# design.net
KiCad netlist of a schematic drawn in Altium Designer
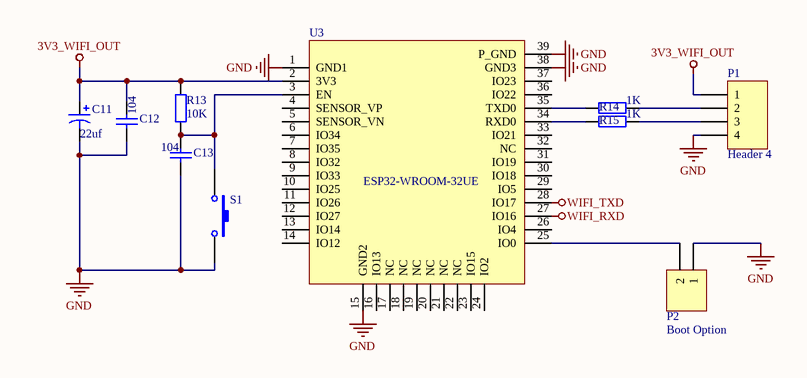
[diagram p0: 转接板.SchDoc]

(export (version "E")
  (design (tool "Eeschema 10.0.6"))
  (components
    (comp (ref "C11")
      (value "22uf")
      (footprint "RB7.6-15")
      (description "Polarized Capacitor (Radial)")
      (fields (field (name "Comment") "Cap Pol1") (field (name "PUBLISHER") "Altium Limited"))
      (libsource (lib "Miscellaneous Devices") (part "Cap Pol1"))
    )
    (comp (ref "C12")
      (value "104")
      (footprint "0805-JT")
      (description "Capacitor")
      (fields (field (name "Comment") "Cap") (field (name "PUBLISHER") "Altium Limited"))
      (libsource (lib "Miscellaneous Devices") (part "Cap"))
    )
    (comp (ref "C13")
      (value "104")
      (footprint "0805-JT")
      (description "Capacitor")
      (fields (field (name "Comment") "Cap") (field (name "PUBLISHER") "Altium Limited"))
      (libsource (lib "Miscellaneous Devices") (part "Cap"))
    )
    (comp (ref "P1")
      (value "Header 4")
      (footprint "HDR1X4")
      (description "Header, 4-Pin")
      (fields (field (name "PUBLISHER") "Altium Limited"))
      (libsource (lib "Miscellaneous Connectors") (part "Header 4"))
    )
    (comp (ref "P2")
      (value "Boot Option")
      (footprint "HDR1X2")
      (description "Header, 2-Pin")
      (fields (field (name "PUBLISHER") "Altium Limited"))
      (libsource (lib "Miscellaneous Connectors") (part "Header 2"))
    )
    (comp (ref "R13")
      (value "10K")
      (footprint "0603-JT")
      (description "Resistor")
      (fields (field (name "Comment") "Res2") (field (name "PUBLISHER") "Altium Limited"))
      (libsource (lib "") (part "Res2_1"))
    )
    (comp (ref "R14")
      (value "1K")
      (footprint "0603-JT")
      (description "Resistor")
      (fields (field (name "Comment") "Res2") (field (name "PUBLISHER") "Altium Limited"))
      (libsource (lib "Miscellaneous Devices") (part "Res2"))
    )
    (comp (ref "R15")
      (value "1K")
      (footprint "0603-JT")
      (description "Resistor")
      (fields (field (name "Comment") "Res2") (field (name "PUBLISHER") "Altium Limited"))
      (libsource (lib "Miscellaneous Devices") (part "Res2"))
    )
    (comp (ref "S1")
      (value "SW-PB")
      (footprint "SPST-2")
      (description "Switch")
      (fields (field (name "PUBLISHER") "Altium Limited"))
      (libsource (lib "Miscellaneous Devices") (part "SW-PB"))
    )
    (comp (ref "U3")
      (value "ESP32-WROOM-32UE")
      (description "ESP32 wifi模块 IPEX接口天线")
      (libsource (lib "原理图库") (part "ESP32-WROOM-32UE"))
    )
  )
  (nets
    (net (code "1") (name "3V3_WIFI_OUT") (class "Default")
      (node (ref "C11") (pin "1") (pinfunction "1_1") (pintype "passive"))
      (node (ref "C12") (pin "2") (pinfunction "2_2") (pintype "passive"))
      (node (ref "P1") (pin "1") (pinfunction "1_1") (pintype "passive"))
      (node (ref "R13") (pin "1") (pinfunction "1_1") (pintype "passive"))
      (node (ref "U3") (pin "2") (pinfunction "3V3_2") (pintype "passive"))
    )
    (net (code "2") (name "GND") (class "Default")
      (node (ref "C11") (pin "2") (pinfunction "2_2") (pintype "passive"))
      (node (ref "C12") (pin "1") (pinfunction "1_1") (pintype "passive"))
      (node (ref "C13") (pin "1") (pinfunction "1_1") (pintype "passive"))
      (node (ref "P1") (pin "4") (pinfunction "4_4") (pintype "passive"))
      (node (ref "P2") (pin "1") (pinfunction "1_1") (pintype "passive"))
      (node (ref "S1") (pin "2") (pinfunction "2_2") (pintype "passive"))
      (node (ref "U3") (pin "1") (pinfunction "GND1_1") (pintype "passive"))
      (node (ref "U3") (pin "15") (pinfunction "GND2_15") (pintype "passive"))
      (node (ref "U3") (pin "38") (pinfunction "GND3_38") (pintype "passive"))
      (node (ref "U3") (pin "39") (pinfunction "P_GND_39") (pintype "passive"))
    )
    (net (code "3") (name "Net-(P1-Pad2)") (class "Default")
      (node (ref "P1") (pin "2") (pinfunction "2_2") (pintype "passive"))
      (node (ref "R14") (pin "2") (pinfunction "2_2") (pintype "passive"))
    )
    (net (code "4") (name "Net-(P1-Pad3)") (class "Default")
      (node (ref "P1") (pin "3") (pinfunction "3_3") (pintype "passive"))
      (node (ref "R15") (pin "2") (pinfunction "2_2") (pintype "passive"))
    )
    (net (code "5") (name "Net-(U3-EN)") (class "Default")
      (node (ref "C13") (pin "2") (pinfunction "2_2") (pintype "passive"))
      (node (ref "R13") (pin "2") (pinfunction "2_2") (pintype "passive"))
      (node (ref "S1") (pin "1") (pinfunction "1_1") (pintype "passive"))
      (node (ref "U3") (pin "3") (pinfunction "EN_3") (pintype "passive"))
    )
    (net (code "6") (name "Net-(U3-IO0)") (class "Default")
      (node (ref "P2") (pin "2") (pinfunction "2_2") (pintype "passive"))
      (node (ref "U3") (pin "25") (pinfunction "IO0_25") (pintype "passive"))
    )
    (net (code "7") (name "Net-(U3-RXD0)") (class "Default")
      (node (ref "R15") (pin "1") (pinfunction "1_1") (pintype "passive"))
      (node (ref "U3") (pin "34") (pinfunction "RXD0_34") (pintype "passive"))
    )
    (net (code "8") (name "Net-(U3-TXD0)") (class "Default")
      (node (ref "R14") (pin "1") (pinfunction "1_1") (pintype "passive"))
      (node (ref "U3") (pin "35") (pinfunction "TXD0_35") (pintype "passive"))
    )
    (net (code "9") (name "WIFI_RXD") (class "Default")
      (node (ref "U3") (pin "27") (pinfunction "IO16_27") (pintype "passive"))
    )
    (net (code "10") (name "WIFI_TXD") (class "Default")
      (node (ref "U3") (pin "28") (pinfunction "IO17_28") (pintype "passive"))
    )
    (net (code "11") (name "unconnected-(U3-IO2-Pad24)") (class "Default")
      (node (ref "U3") (pin "24") (pinfunction "IO2_24") (pintype "passive"))
    )
    (net (code "12") (name "unconnected-(U3-IO4-Pad26)") (class "Default")
      (node (ref "U3") (pin "26") (pinfunction "IO4_26") (pintype "passive"))
    )
    (net (code "13") (name "unconnected-(U3-IO5-Pad29)") (class "Default")
      (node (ref "U3") (pin "29") (pinfunction "IO5_29") (pintype "passive"))
    )
    (net (code "14") (name "unconnected-(U3-IO12-Pad14)") (class "Default")
      (node (ref "U3") (pin "14") (pinfunction "IO12_14") (pintype "passive"))
    )
    (net (code "15") (name "unconnected-(U3-IO13-Pad16)") (class "Default")
      (node (ref "U3") (pin "16") (pinfunction "IO13_16") (pintype "passive"))
    )
    (net (code "16") (name "unconnected-(U3-IO14-Pad13)") (class "Default")
      (node (ref "U3") (pin "13") (pinfunction "IO14_13") (pintype "passive"))
    )
    (net (code "17") (name "unconnected-(U3-IO15-Pad23)") (class "Default")
      (node (ref "U3") (pin "23") (pinfunction "IO15_23") (pintype "passive"))
    )
    (net (code "18") (name "unconnected-(U3-IO18-Pad30)") (class "Default")
      (node (ref "U3") (pin "30") (pinfunction "IO18_30") (pintype "passive"))
    )
    (net (code "19") (name "unconnected-(U3-IO19-Pad31)") (class "Default")
      (node (ref "U3") (pin "31") (pinfunction "IO19_31") (pintype "passive"))
    )
    (net (code "20") (name "unconnected-(U3-IO21-Pad33)") (class "Default")
      (node (ref "U3") (pin "33") (pinfunction "IO21_33") (pintype "passive"))
    )
    (net (code "21") (name "unconnected-(U3-IO22-Pad36)") (class "Default")
      (node (ref "U3") (pin "36") (pinfunction "IO22_36") (pintype "passive"))
    )
    (net (code "22") (name "unconnected-(U3-IO23-Pad37)") (class "Default")
      (node (ref "U3") (pin "37") (pinfunction "IO23_37") (pintype "passive"))
    )
    (net (code "23") (name "unconnected-(U3-IO25-Pad10)") (class "Default")
      (node (ref "U3") (pin "10") (pinfunction "IO25_10") (pintype "passive"))
    )
    (net (code "24") (name "unconnected-(U3-IO26-Pad11)") (class "Default")
      (node (ref "U3") (pin "11") (pinfunction "IO26_11") (pintype "passive"))
    )
    (net (code "25") (name "unconnected-(U3-IO27-Pad12)") (class "Default")
      (node (ref "U3") (pin "12") (pinfunction "IO27_12") (pintype "passive"))
    )
    (net (code "26") (name "unconnected-(U3-IO32-Pad8)") (class "Default")
      (node (ref "U3") (pin "8") (pinfunction "IO32_8") (pintype "passive"))
    )
    (net (code "27") (name "unconnected-(U3-IO33-Pad9)") (class "Default")
      (node (ref "U3") (pin "9") (pinfunction "IO33_9") (pintype "passive"))
    )
    (net (code "28") (name "unconnected-(U3-IO34-Pad6)") (class "Default")
      (node (ref "U3") (pin "6") (pinfunction "IO34_6") (pintype "passive"))
    )
    (net (code "29") (name "unconnected-(U3-IO35-Pad7)") (class "Default")
      (node (ref "U3") (pin "7") (pinfunction "IO35_7") (pintype "passive"))
    )
    (net (code "30") (name "unconnected-(U3-NC-Pad17)") (class "Default")
      (node (ref "U3") (pin "17") (pinfunction "NC_17") (pintype "passive"))
    )
    (net (code "31") (name "unconnected-(U3-NC-Pad18)") (class "Default")
      (node (ref "U3") (pin "18") (pinfunction "NC_18") (pintype "passive"))
    )
    (net (code "32") (name "unconnected-(U3-NC-Pad19)") (class "Default")
      (node (ref "U3") (pin "19") (pinfunction "NC_19") (pintype "passive"))
    )
    (net (code "33") (name "unconnected-(U3-NC-Pad20)") (class "Default")
      (node (ref "U3") (pin "20") (pinfunction "NC_20") (pintype "passive"))
    )
    (net (code "34") (name "unconnected-(U3-NC-Pad21)") (class "Default")
      (node (ref "U3") (pin "21") (pinfunction "NC_21") (pintype "passive"))
    )
    (net (code "35") (name "unconnected-(U3-NC-Pad22)") (class "Default")
      (node (ref "U3") (pin "22") (pinfunction "NC_22") (pintype "passive"))
    )
    (net (code "36") (name "unconnected-(U3-NC-Pad32)") (class "Default")
      (node (ref "U3") (pin "32") (pinfunction "NC_32") (pintype "passive"))
    )
    (net (code "37") (name "unconnected-(U3-SENSOR_VN-Pad5)") (class "Default")
      (node (ref "U3") (pin "5") (pinfunction "SENSOR_VN_5") (pintype "passive"))
    )
    (net (code "38") (name "unconnected-(U3-SENSOR_VP-Pad4)") (class "Default")
      (node (ref "U3") (pin "4") (pinfunction "SENSOR_VP_4") (pintype "passive"))
    )
  )
)
